# Eth_DP83848.net
KiCad netlist of a schematic drawn in Altium Designer
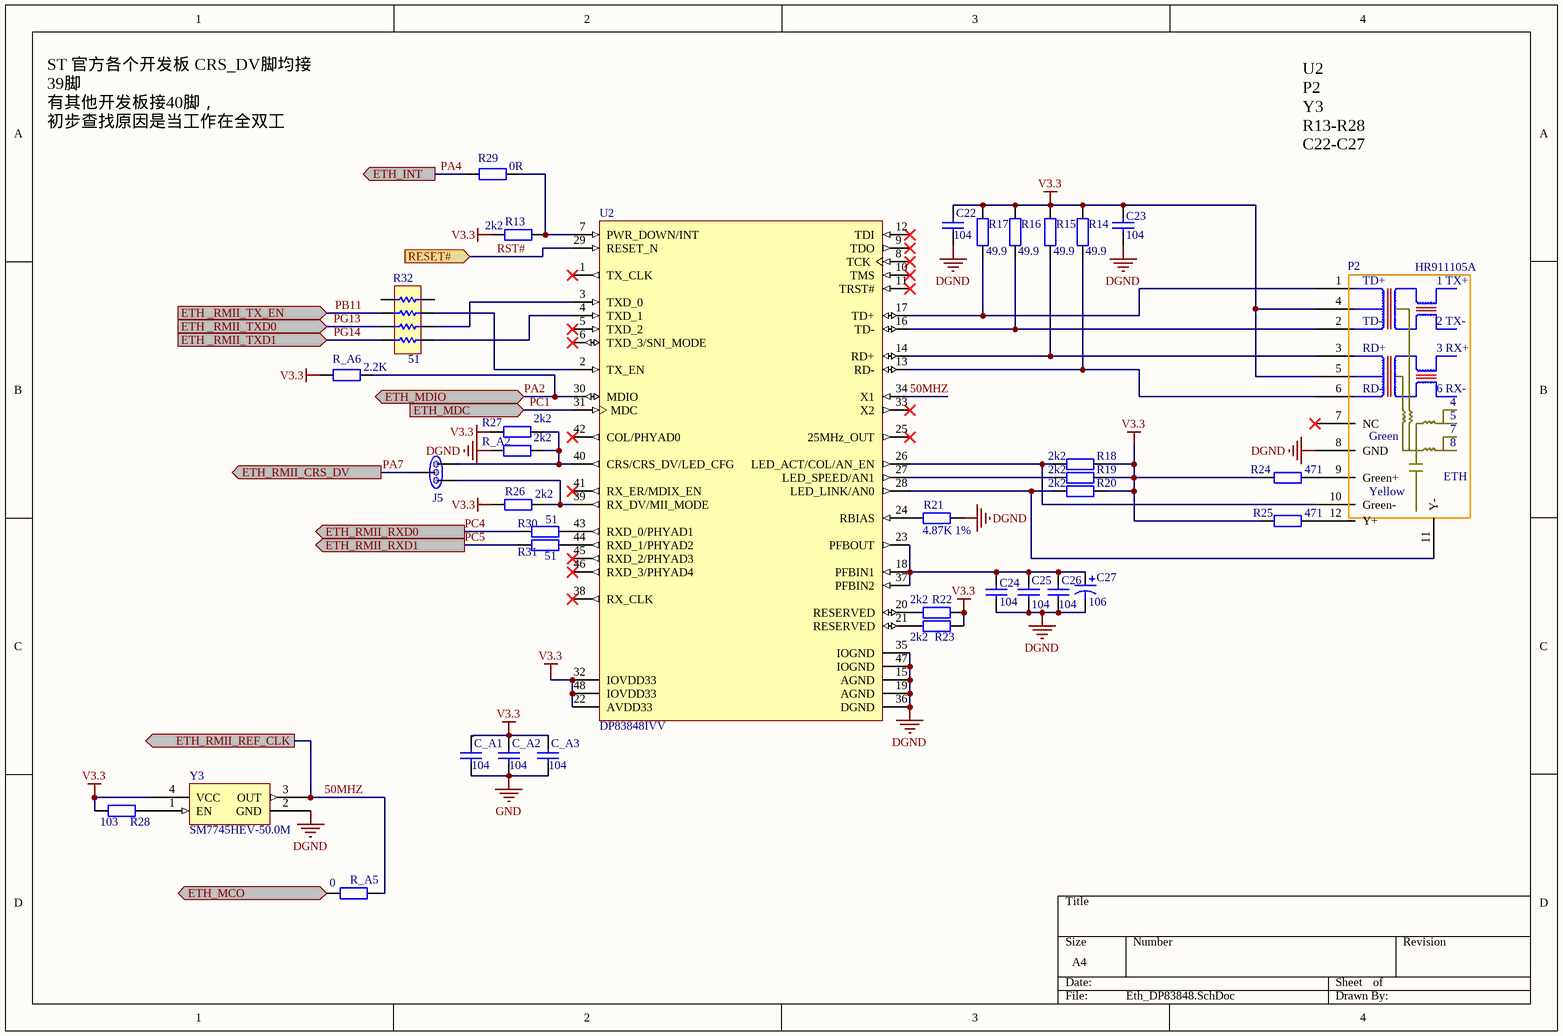
[diagram p0: Eth_DP83848.SchDoc]

(export (version "E")
  (design (tool "Eeschema 10.0.6"))
  (components
    (comp (ref "C22")
      (value "104")
      (footprint "RESC1608L")
      (description "Capacitor")
      (fields (field (name "Comment") "Cap") (field (name "PUBLISHER") "Altium Limited"))
      (libsource (lib "Miscellaneous Devices") (part "Cap"))
    )
    (comp (ref "C23")
      (value "104")
      (footprint "RESC1608L")
      (description "Capacitor")
      (fields (field (name "Comment") "Cap") (field (name "PUBLISHER") "Altium Limited"))
      (libsource (lib "Miscellaneous Devices") (part "Cap"))
    )
    (comp (ref "C24")
      (value "104")
      (footprint "RESC1608L")
      (description "Capacitor")
      (fields (field (name "Comment") "Cap") (field (name "PUBLISHER") "Altium Limited"))
      (libsource (lib "Miscellaneous Devices") (part "Cap"))
    )
    (comp (ref "C25")
      (value "104")
      (footprint "RESC1608L")
      (description "Capacitor")
      (fields (field (name "Comment") "Cap") (field (name "PUBLISHER") "Altium Limited"))
      (libsource (lib "Miscellaneous Devices") (part "Cap"))
    )
    (comp (ref "C26")
      (value "104")
      (footprint "RESC1608L")
      (description "Capacitor")
      (fields (field (name "Comment") "Cap") (field (name "PUBLISHER") "Altium Limited"))
      (libsource (lib "Miscellaneous Devices") (part "Cap"))
    )
    (comp (ref "C27")
      (value "106")
      (footprint "C3216A")
      (description "Polarized Capacitor (Radial)")
      (fields (field (name "Comment") "Cap Pol1") (field (name "PUBLISHER") "Altium Limited"))
      (libsource (lib "Miscellaneous Devices") (part "Cap Pol1"))
    )
    (comp (ref "C_A1")
      (value "104")
      (footprint "RESC1608L")
      (description "Capacitor")
      (fields (field (name "Comment") "Cap") (field (name "PUBLISHER") "Altium Limited"))
      (libsource (lib "Miscellaneous Devices") (part "Cap"))
    )
    (comp (ref "C_A2")
      (value "104")
      (footprint "RESC1608L")
      (description "Capacitor")
      (fields (field (name "Comment") "Cap") (field (name "PUBLISHER") "Altium Limited"))
      (libsource (lib "Miscellaneous Devices") (part "Cap"))
    )
    (comp (ref "C_A3")
      (value "104")
      (footprint "RESC1608L")
      (description "Capacitor")
      (fields (field (name "Comment") "Cap") (field (name "PUBLISHER") "Altium Limited"))
      (libsource (lib "Miscellaneous Devices") (part "Cap"))
    )
    (comp (ref "J5") (value "3P") (footprint "SEC-3PIN-0805") (libsource (lib "Kyle_Sch") (part "3P")))
    (comp (ref "P2")
      (value "HR911105A")
      (footprint "HR911105A")
      (libsource (lib "Kyle_Sch") (part "HR911105A"))
    )
    (comp (ref "R13")
      (value "2k2")
      (footprint "RESC1608L")
      (description "Resistor")
      (fields (field (name "Comment") "Res2") (field (name "PUBLISHER") "Altium Limited"))
      (libsource (lib "Miscellaneous Devices") (part "Res2"))
    )
    (comp (ref "R14")
      (value "49.9")
      (footprint "RESC1608L")
      (description "Resistor")
      (fields (field (name "Comment") "Res2") (field (name "PUBLISHER") "Altium Limited"))
      (libsource (lib "") (part "Res2_1"))
    )
    (comp (ref "R15")
      (value "49.9")
      (footprint "RESC1608L")
      (description "Resistor")
      (fields (field (name "Comment") "Res2") (field (name "PUBLISHER") "Altium Limited"))
      (libsource (lib "") (part "Res2_1"))
    )
    (comp (ref "R16")
      (value "49.9")
      (footprint "RESC1608L")
      (description "Resistor")
      (fields (field (name "Comment") "Res2") (field (name "PUBLISHER") "Altium Limited"))
      (libsource (lib "") (part "Res2_1"))
    )
    (comp (ref "R17")
      (value "49.9")
      (footprint "RESC1608L")
      (description "Resistor")
      (fields (field (name "Comment") "Res2") (field (name "PUBLISHER") "Altium Limited"))
      (libsource (lib "") (part "Res2_1"))
    )
    (comp (ref "R18")
      (value "2k2")
      (footprint "RESC1608L")
      (description "Resistor")
      (fields (field (name "Comment") "Res2") (field (name "PUBLISHER") "Altium Limited"))
      (libsource (lib "Miscellaneous Devices") (part "Res2"))
    )
    (comp (ref "R19")
      (value "2k2")
      (footprint "RESC1608L")
      (description "Resistor")
      (fields (field (name "Comment") "Res2") (field (name "PUBLISHER") "Altium Limited"))
      (libsource (lib "Miscellaneous Devices") (part "Res2"))
    )
    (comp (ref "R20")
      (value "2k2")
      (footprint "RESC1608L")
      (description "Resistor")
      (fields (field (name "Comment") "Res2") (field (name "PUBLISHER") "Altium Limited"))
      (libsource (lib "Miscellaneous Devices") (part "Res2"))
    )
    (comp (ref "R21")
      (value "4.87K 1%")
      (footprint "RESC1608L")
      (description "Resistor")
      (fields (field (name "Comment") "Res2") (field (name "PUBLISHER") "Altium Limited"))
      (libsource (lib "Miscellaneous Devices") (part "Res2"))
    )
    (comp (ref "R22")
      (value "2k2")
      (footprint "RESC1608L")
      (description "Resistor")
      (fields (field (name "Comment") "Res2") (field (name "PUBLISHER") "Altium Limited"))
      (libsource (lib "Miscellaneous Devices") (part "Res2"))
    )
    (comp (ref "R23")
      (value "2k2")
      (footprint "RESC1608L")
      (description "Resistor")
      (fields (field (name "Comment") "Res2") (field (name "PUBLISHER") "Altium Limited"))
      (libsource (lib "Miscellaneous Devices") (part "Res2"))
    )
    (comp (ref "R24")
      (value "471")
      (footprint "RESC1608L")
      (description "Resistor")
      (fields (field (name "Comment") "Res2") (field (name "PUBLISHER") "Altium Limited"))
      (libsource (lib "Miscellaneous Devices") (part "Res2"))
    )
    (comp (ref "R25")
      (value "471")
      (footprint "RESC1608L")
      (description "Resistor")
      (fields (field (name "Comment") "Res2") (field (name "PUBLISHER") "Altium Limited"))
      (libsource (lib "Miscellaneous Devices") (part "Res2"))
    )
    (comp (ref "R26")
      (value "2k2")
      (footprint "RESC1608L")
      (description "Resistor")
      (fields (field (name "Comment") "Res2") (field (name "PUBLISHER") "Altium Limited"))
      (libsource (lib "Miscellaneous Devices") (part "Res2"))
    )
    (comp (ref "R27")
      (value "2k2")
      (footprint "RESC1608L")
      (description "Resistor")
      (fields (field (name "Comment") "Res2") (field (name "PUBLISHER") "Altium Limited"))
      (libsource (lib "") (part "Res2_2"))
    )
    (comp (ref "R28")
      (value "103")
      (footprint "RESC1608L")
      (description "Resistor")
      (fields (field (name "Comment") "Res2") (field (name "PUBLISHER") "Altium Limited"))
      (libsource (lib "") (part "Res2_2"))
    )
    (comp (ref "R29")
      (value "0R")
      (footprint "RESC1608L")
      (description "Resistor")
      (fields (field (name "Comment") "Res2") (field (name "PUBLISHER") "Altium Limited"))
      (libsource (lib "Miscellaneous Devices") (part "Res2"))
    )
    (comp (ref "R30")
      (value "51")
      (footprint "RESC1608L")
      (description "Resistor")
      (fields (field (name "Comment") "Res2") (field (name "PUBLISHER") "Altium Limited"))
      (libsource (lib "Miscellaneous Devices") (part "Res2"))
    )
    (comp (ref "R31")
      (value "51")
      (footprint "RESC1608L")
      (description "Resistor")
      (fields (field (name "Comment") "Res2") (field (name "PUBLISHER") "Altium Limited"))
      (libsource (lib "Miscellaneous Devices") (part "Res2"))
    )
    (comp (ref "R32")
      (value "51")
      (footprint "8P4R_0603")
      (fields (field (name "Comment") "0603-4R"))
      (libsource (lib "STM32-DemoPCB_lib") (part "Resister Array"))
    )
    (comp (ref "R_A2")
      (value "2k2")
      (footprint "RESC1608L")
      (description "Resistor")
      (fields (field (name "Comment") "Res2") (field (name "PUBLISHER") "Altium Limited"))
      (libsource (lib "") (part "Res2_2"))
    )
    (comp (ref "R_A5")
      (value "0")
      (footprint "RESC1608L")
      (description "Resistor")
      (fields (field (name "Comment") "Res2") (field (name "PUBLISHER") "Altium Limited"))
      (libsource (lib "Miscellaneous Devices") (part "Res2"))
    )
    (comp (ref "R_A6")
      (value "2.2K")
      (footprint "RESC1608L")
      (description "Resistor")
      (fields (field (name "Comment") "Res2") (field (name "PUBLISHER") "Altium Limited"))
      (libsource (lib "Miscellaneous Devices") (part "Res2"))
    )
    (comp (ref "U2")
      (value "DP83848IVV")
      (footprint "VBH48A_N")
      (description "PHYTER?Industrial Temperature Single Port 10/100 Mb/s Ethernet Physical Layer Transceiver")
      (fields
        (field (name "MANUFACTURER") "National Semiconductor")
        (field (name "DIGIKEYPARTNUMBER") "DP83848IVV-ND")
        (field (name "PUBLISHER") "Altium Limited")
      )
      (libsource (lib "NSC Interface") (part "DP83848IVV"))
    )
    (comp (ref "Y3")
      (value "SM7745HEV-50.0M")
      (footprint "XTAL_5X7")
      (libsource (lib "STM32-DemoPCB_lib") (part "SM7745HEV-50.0M"))
    )
  )
  (nets
    (net (code "1") (name "/50MHZ") (class "Default")
      (node (ref "R_A5") (pin "2") (pinfunction "2_2") (pintype "passive"))
      (node (ref "U2") (pin "34") (pinfunction "X1_34") (pintype "input"))
      (node (ref "Y3") (pin "3") (pinfunction "OUT_3") (pintype "output"))
    )
    (net (code "2") (name "/ETH_MCO") (class "Default")
      (node (ref "R_A5") (pin "1") (pinfunction "1_1") (pintype "passive"))
    )
    (net (code "3") (name "/PA2") (class "Default")
      (node (ref "R_A6") (pin "2") (pinfunction "2_2") (pintype "passive"))
      (node (ref "U2") (pin "30") (pinfunction "MDIO_30") (pintype "bidirectional"))
    )
    (net (code "4") (name "/PA4") (class "Default")
      (node (ref "R29") (pin "1") (pinfunction "1_1") (pintype "passive"))
    )
    (net (code "5") (name "/PA7") (class "Default")
      (node (ref "J5") (pin "2") (pinfunction "2_2") (pintype "passive"))
    )
    (net (code "6") (name "/PB11") (class "Default")
      (node (ref "R32") (pin "3") (pinfunction "3_3") (pintype "passive"))
    )
    (net (code "7") (name "/PC1") (class "Default")
      (node (ref "U2") (pin "31") (pinfunction "MDC_31") (pintype "input"))
    )
    (net (code "8") (name "/PC4") (class "Default")
      (node (ref "R30") (pin "1") (pinfunction "1_1") (pintype "passive"))
    )
    (net (code "9") (name "/PC5") (class "Default")
      (node (ref "R31") (pin "1") (pinfunction "1_1") (pintype "passive"))
    )
    (net (code "10") (name "/PG13") (class "Default")
      (node (ref "R32") (pin "5") (pinfunction "5_5") (pintype "passive"))
    )
    (net (code "11") (name "/PG14") (class "Default")
      (node (ref "R32") (pin "7") (pinfunction "7_7") (pintype "passive"))
    )
    (net (code "12") (name "/RST#") (class "Default")
      (node (ref "U2") (pin "29") (pinfunction "RESET_N_29") (pintype "input"))
    )
    (net (code "13") (name "DGND") (class "Default")
      (node (ref "C22") (pin "1") (pinfunction "1_1") (pintype "passive"))
      (node (ref "C23") (pin "1") (pinfunction "1_1") (pintype "passive"))
      (node (ref "C24") (pin "1") (pinfunction "1_1") (pintype "passive"))
      (node (ref "C25") (pin "1") (pinfunction "1_1") (pintype "passive"))
      (node (ref "C26") (pin "1") (pinfunction "1_1") (pintype "passive"))
      (node (ref "C27") (pin "2") (pinfunction "2_2") (pintype "passive"))
      (node (ref "P2") (pin "8") (pinfunction "GND_8") (pintype "passive"))
      (node (ref "R21") (pin "2") (pinfunction "2_2") (pintype "passive"))
      (node (ref "R_A2") (pin "2") (pinfunction "2_2") (pintype "passive"))
      (node (ref "U2") (pin "15") (pinfunction "AGND_15") (pintype "power_in"))
      (node (ref "U2") (pin "19") (pinfunction "AGND_19") (pintype "power_in"))
      (node (ref "U2") (pin "35") (pinfunction "IOGND_35") (pintype "power_in"))
      (node (ref "U2") (pin "36") (pinfunction "DGND_36") (pintype "power_in"))
      (node (ref "U2") (pin "47") (pinfunction "IOGND_47") (pintype "power_in"))
      (node (ref "Y3") (pin "2") (pinfunction "GND_2") (pintype "passive"))
    )
    (net (code "14") (name "GND") (class "Default")
      (node (ref "C_A1") (pin "1") (pinfunction "1_1") (pintype "passive"))
      (node (ref "C_A2") (pin "1") (pinfunction "1_1") (pintype "passive"))
      (node (ref "C_A3") (pin "1") (pinfunction "1_1") (pintype "passive"))
    )
    (net (code "15") (name "Net-(P2-Green+)") (class "Default")
      (node (ref "P2") (pin "9") (pinfunction "Green+_9") (pintype "passive"))
      (node (ref "R24") (pin "2") (pinfunction "2_2") (pintype "passive"))
    )
    (net (code "16") (name "Net-(P2-Green-)") (class "Default")
      (node (ref "P2") (pin "10") (pinfunction "Green-_10") (pintype "passive"))
      (node (ref "R18") (pin "1") (pinfunction "1_1") (pintype "passive"))
      (node (ref "U2") (pin "26") (pinfunction "LED_ACT/COL/AN_EN_26") (pintype "output"))
    )
    (net (code "17") (name "Net-(P2-Y+)") (class "Default")
      (node (ref "P2") (pin "12") (pinfunction "Y+_12") (pintype "passive"))
      (node (ref "R25") (pin "2") (pinfunction "2_2") (pintype "passive"))
    )
    (net (code "18") (name "Net-(P2-Y-)") (class "Default")
      (node (ref "P2") (pin "11") (pinfunction "Y-_11") (pintype "passive"))
      (node (ref "R20") (pin "1") (pinfunction "1_1") (pintype "passive"))
      (node (ref "U2") (pin "28") (pinfunction "LED_LINK/AN0_28") (pintype "output"))
    )
    (net (code "19") (name "Net-(R22-Pad1)") (class "Default")
      (node (ref "R22") (pin "1") (pinfunction "1_1") (pintype "passive"))
      (node (ref "U2") (pin "20") (pinfunction "RESERVED_20") (pintype "bidirectional"))
    )
    (net (code "20") (name "Net-(R23-Pad1)") (class "Default")
      (node (ref "R23") (pin "1") (pinfunction "1_1") (pintype "passive"))
      (node (ref "U2") (pin "21") (pinfunction "RESERVED_21") (pintype "bidirectional"))
    )
    (net (code "21") (name "Net-(U2-CRS{slash}CRS_DV{slash}LED_CFG)") (class "Default")
      (node (ref "J5") (pin "1") (pinfunction "1_1") (pintype "passive"))
      (node (ref "R27") (pin "1") (pinfunction "1_1") (pintype "passive"))
      (node (ref "R_A2") (pin "1") (pinfunction "1_1") (pintype "passive"))
      (node (ref "U2") (pin "40") (pinfunction "CRS/CRS_DV/LED_CFG_40") (pintype "output"))
    )
    (net (code "22") (name "Net-(U2-LED_SPEED{slash}AN1)") (class "Default")
      (node (ref "R19") (pin "1") (pinfunction "1_1") (pintype "passive"))
      (node (ref "U2") (pin "27") (pinfunction "LED_SPEED/AN1_27") (pintype "output"))
    )
    (net (code "23") (name "Net-(U2-PFBIN1)") (class "Default")
      (node (ref "C24") (pin "2") (pinfunction "2_2") (pintype "passive"))
      (node (ref "C25") (pin "2") (pinfunction "2_2") (pintype "passive"))
      (node (ref "C26") (pin "2") (pinfunction "2_2") (pintype "passive"))
      (node (ref "C27") (pin "1") (pinfunction "1_1") (pintype "passive"))
      (node (ref "U2") (pin "18") (pinfunction "PFBIN1_18") (pintype "input"))
      (node (ref "U2") (pin "23") (pinfunction "PFBOUT_23") (pintype "output"))
      (node (ref "U2") (pin "37") (pinfunction "PFBIN2_37") (pintype "input"))
    )
    (net (code "24") (name "Net-(U2-PWR_DOWN{slash}INT)") (class "Default")
      (node (ref "R13") (pin "2") (pinfunction "2_2") (pintype "passive"))
      (node (ref "R29") (pin "2") (pinfunction "2_2") (pintype "passive"))
      (node (ref "U2") (pin "7") (pinfunction "PWR_DOWN/INT_7") (pintype "input"))
    )
    (net (code "25") (name "Net-(U2-RBIAS)") (class "Default")
      (node (ref "R21") (pin "1") (pinfunction "1_1") (pintype "passive"))
      (node (ref "U2") (pin "24") (pinfunction "RBIAS_24") (pintype "input"))
    )
    (net (code "26") (name "Net-(U2-RD+)") (class "Default")
      (node (ref "P2") (pin "3") (pintype "passive"))
      (node (ref "R15") (pin "1") (pinfunction "1_1") (pintype "passive"))
      (node (ref "U2") (pin "14") (pinfunction "RD+_14") (pintype "bidirectional"))
    )
    (net (code "27") (name "Net-(U2-RD-)") (class "Default")
      (node (ref "P2") (pin "6") (pintype "passive"))
      (node (ref "R14") (pin "1") (pinfunction "1_1") (pintype "passive"))
      (node (ref "U2") (pin "13") (pinfunction "RD-_13") (pintype "bidirectional"))
    )
    (net (code "28") (name "Net-(U2-RXD_0{slash}PHYAD1)") (class "Default")
      (node (ref "R30") (pin "2") (pinfunction "2_2") (pintype "passive"))
      (node (ref "U2") (pin "43") (pinfunction "RXD_0/PHYAD1_43") (pintype "output"))
    )
    (net (code "29") (name "Net-(U2-RXD_1{slash}PHYAD2)") (class "Default")
      (node (ref "R31") (pin "2") (pinfunction "2_2") (pintype "passive"))
      (node (ref "U2") (pin "44") (pinfunction "RXD_1/PHYAD2_44") (pintype "output"))
    )
    (net (code "30") (name "Net-(U2-RX_DV{slash}MII_MODE)") (class "Default")
      (node (ref "J5") (pin "3") (pinfunction "3_3") (pintype "passive"))
      (node (ref "R26") (pin "2") (pinfunction "2_2") (pintype "passive"))
      (node (ref "U2") (pin "39") (pinfunction "RX_DV/MII_MODE_39") (pintype "output"))
    )
    (net (code "31") (name "Net-(U2-TD+)") (class "Default")
      (node (ref "P2") (pin "1") (pintype "passive"))
      (node (ref "R17") (pin "1") (pinfunction "1_1") (pintype "passive"))
      (node (ref "U2") (pin "17") (pinfunction "TD+_17") (pintype "bidirectional"))
    )
    (net (code "32") (name "Net-(U2-TD-)") (class "Default")
      (node (ref "P2") (pin "2") (pintype "passive"))
      (node (ref "R16") (pin "1") (pinfunction "1_1") (pintype "passive"))
      (node (ref "U2") (pin "16") (pinfunction "TD-_16") (pintype "bidirectional"))
    )
    (net (code "33") (name "Net-(U2-TXD_0)") (class "Default")
      (node (ref "R32") (pin "6") (pinfunction "6_6") (pintype "passive"))
      (node (ref "U2") (pin "3") (pinfunction "TXD_0_3") (pintype "input"))
    )
    (net (code "34") (name "Net-(U2-TXD_1)") (class "Default")
      (node (ref "R32") (pin "8") (pinfunction "8_8") (pintype "passive"))
      (node (ref "U2") (pin "4") (pinfunction "TXD_1_4") (pintype "input"))
    )
    (net (code "35") (name "Net-(U2-TX_EN)") (class "Default")
      (node (ref "R32") (pin "4") (pinfunction "4_4") (pintype "passive"))
      (node (ref "U2") (pin "2") (pinfunction "TX_EN_2") (pintype "input"))
    )
    (net (code "36") (name "Net-(Y3-EN)") (class "Default")
      (node (ref "R28") (pin "1") (pinfunction "1_1") (pintype "passive"))
      (node (ref "Y3") (pin "1") (pinfunction "EN_1") (pintype "input"))
    )
    (net (code "37") (name "V3.3") (class "Default")
      (node (ref "C22") (pin "2") (pinfunction "2_2") (pintype "passive"))
      (node (ref "C23") (pin "2") (pinfunction "2_2") (pintype "passive"))
      (node (ref "C_A2") (pin "2") (pinfunction "2_2") (pintype "passive"))
      (node (ref "C_A3") (pin "2") (pinfunction "2_2") (pintype "passive"))
      (node (ref "P2") (pin "4") (pintype "passive"))
      (node (ref "P2") (pin "5") (pintype "passive"))
      (node (ref "R13") (pin "1") (pinfunction "1_1") (pintype "passive"))
      (node (ref "R14") (pin "2") (pinfunction "2_2") (pintype "passive"))
      (node (ref "R15") (pin "2") (pinfunction "2_2") (pintype "passive"))
      (node (ref "R16") (pin "2") (pinfunction "2_2") (pintype "passive"))
      (node (ref "R17") (pin "2") (pinfunction "2_2") (pintype "passive"))
      (node (ref "R18") (pin "2") (pinfunction "2_2") (pintype "passive"))
      (node (ref "R19") (pin "2") (pinfunction "2_2") (pintype "passive"))
      (node (ref "R20") (pin "2") (pinfunction "2_2") (pintype "passive"))
      (node (ref "R22") (pin "2") (pinfunction "2_2") (pintype "passive"))
      (node (ref "R23") (pin "2") (pinfunction "2_2") (pintype "passive"))
      (node (ref "R24") (pin "1") (pinfunction "1_1") (pintype "passive"))
      (node (ref "R25") (pin "1") (pinfunction "1_1") (pintype "passive"))
      (node (ref "R26") (pin "1") (pinfunction "1_1") (pintype "passive"))
      (node (ref "R27") (pin "2") (pinfunction "2_2") (pintype "passive"))
      (node (ref "R28") (pin "2") (pinfunction "2_2") (pintype "passive"))
      (node (ref "R_A6") (pin "1") (pinfunction "1_1") (pintype "passive"))
      (node (ref "U2") (pin "22") (pinfunction "AVDD33_22") (pintype "power_in"))
      (node (ref "U2") (pin "32") (pinfunction "IOVDD33_32") (pintype "power_in"))
      (node (ref "U2") (pin "48") (pinfunction "IOVDD33_48") (pintype "power_in"))
      (node (ref "Y3") (pin "4") (pinfunction "VCC_4") (pintype "passive"))
    )
    (net (code "38") (name "unconnected-(C_A1-Pad2)") (class "Default")
      (node (ref "C_A1") (pin "2") (pinfunction "2_2") (pintype "passive"))
    )
    (net (code "39") (name "unconnected-(P2-NC-Pad7)") (class "Default")
      (node (ref "P2") (pin "7") (pinfunction "NC_7") (pintype "passive+no_connect"))
    )
    (net (code "40") (name "unconnected-(R32-Pad1)") (class "Default")
      (node (ref "R32") (pin "1") (pinfunction "1_1") (pintype "passive"))
    )
    (net (code "41") (name "unconnected-(R32-Pad2)") (class "Default")
      (node (ref "R32") (pin "2") (pinfunction "2_2") (pintype "passive"))
    )
    (net (code "42") (name "unconnected-(U2-25MHz_OUT-Pad25)") (class "Default")
      (node (ref "U2") (pin "25") (pinfunction "25MHz_OUT_25") (pintype "output+no_connect"))
    )
    (net (code "43") (name "unconnected-(U2-COL{slash}PHYAD0-Pad42)") (class "Default")
      (node (ref "U2") (pin "42") (pinfunction "COL/PHYAD0_42") (pintype "output+no_connect"))
    )
    (net (code "44") (name "unconnected-(U2-RXD_2{slash}PHYAD3-Pad45)") (class "Default")
      (node (ref "U2") (pin "45") (pinfunction "RXD_2/PHYAD3_45") (pintype "output+no_connect"))
    )
    (net (code "45") (name "unconnected-(U2-RXD_3{slash}PHYAD4-Pad46)") (class "Default")
      (node (ref "U2") (pin "46") (pinfunction "RXD_3/PHYAD4_46") (pintype "output+no_connect"))
    )
    (net (code "46") (name "unconnected-(U2-RX_CLK-Pad38)") (class "Default")
      (node (ref "U2") (pin "38") (pinfunction "RX_CLK_38") (pintype "output+no_connect"))
    )
    (net (code "47") (name "unconnected-(U2-RX_ER{slash}MDIX_EN-Pad41)") (class "Default")
      (node (ref "U2") (pin "41") (pinfunction "RX_ER/MDIX_EN_41") (pintype "output+no_connect"))
    )
    (net (code "48") (name "unconnected-(U2-TCK-Pad8)") (class "Default")
      (node (ref "U2") (pin "8") (pinfunction "TCK_8") (pintype "input+no_connect"))
    )
    (net (code "49") (name "unconnected-(U2-TDI-Pad12)") (class "Default")
      (node (ref "U2") (pin "12") (pinfunction "TDI_12") (pintype "input+no_connect"))
    )
    (net (code "50") (name "unconnected-(U2-TDO-Pad9)") (class "Default")
      (node (ref "U2") (pin "9") (pinfunction "TDO_9") (pintype "output+no_connect"))
    )
    (net (code "51") (name "unconnected-(U2-TMS-Pad10)") (class "Default")
      (node (ref "U2") (pin "10") (pinfunction "TMS_10") (pintype "input+no_connect"))
    )
    (net (code "52") (name "unconnected-(U2-TRST#-Pad11)") (class "Default")
      (node (ref "U2") (pin "11") (pinfunction "TRST#_11") (pintype "input+no_connect"))
    )
    (net (code "53") (name "unconnected-(U2-TXD_2-Pad5)") (class "Default")
      (node (ref "U2") (pin "5") (pinfunction "TXD_2_5") (pintype "input+no_connect"))
    )
    (net (code "54") (name "unconnected-(U2-TXD_3{slash}SNI_MODE-Pad6)") (class "Default")
      (node (ref "U2") (pin "6") (pinfunction "TXD_3/SNI_MODE_6") (pintype "bidirectional+no_connect"))
    )
    (net (code "55") (name "unconnected-(U2-TX_CLK-Pad1)") (class "Default")
      (node (ref "U2") (pin "1") (pinfunction "TX_CLK_1") (pintype "output+no_connect"))
    )
    (net (code "56") (name "unconnected-(U2-X2-Pad33)") (class "Default")
      (node (ref "U2") (pin "33") (pinfunction "X2_33") (pintype "output+no_connect"))
    )
  )
)
